# RTU_LMG_DI.net
KiCad netlist of a schematic drawn in Altium Designer
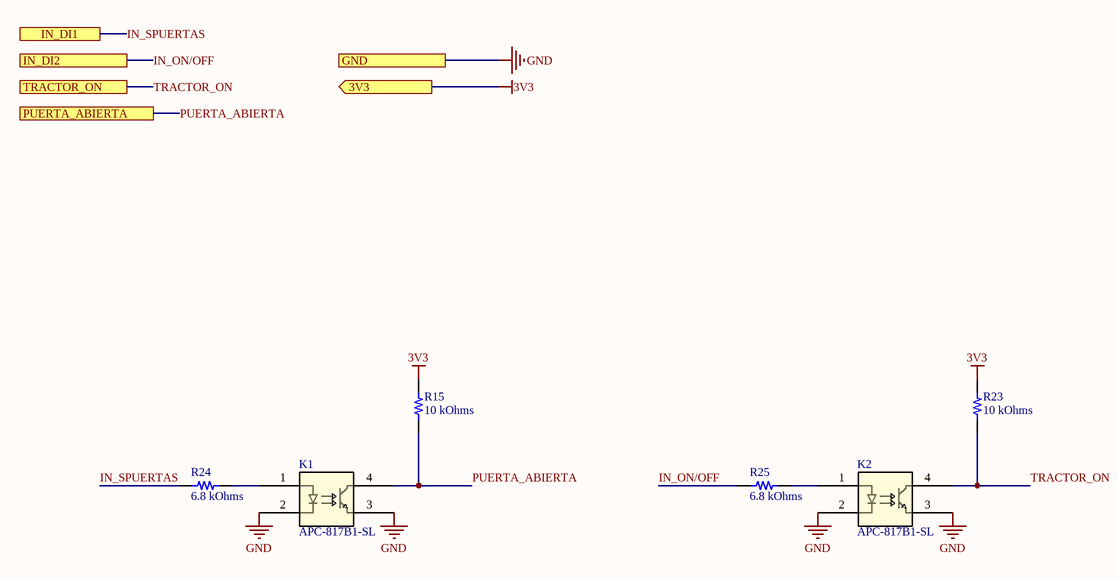
[diagram p0: RTU_LMG_DI.SchDoc]

(export (version "E")
  (design (tool "Eeschema 10.0.6"))
  (components
    (comp (ref "K1")
      (value "APC-817B1-SL")
      (footprint "APC-817xx-SL_AMB")
      (description "Description")
      (fields (field (name "COPYRIGHT") "Copyright (C) 2025 Ultra Librarian. All rights reserved."))
      (libsource (lib "APC-817B1-SL") (part "APC-817B1-SL"))
    )
    (comp (ref "K2")
      (value "APC-817B1-SL")
      (footprint "APC-817xx-SL_AMB")
      (description "Description")
      (fields (field (name "COPYRIGHT") "Copyright (C) 2025 Ultra Librarian. All rights reserved."))
      (libsource (lib "APC-817B1-SL") (part "APC-817B1-SL"))
    )
    (comp (ref "R15")
      (value "10 kOhms")
      (footprint "RES 0603_1608")
      (description "RES 10K OHM 1% 1/10W 0603")
      (fields (field (name "PART NUMBER") "RC0603FR-0710KL") (field (name "MANUFACTURER") "Yageo"))
      (libsource (lib "Celestial Altium Library - altium_library") (part "Resistor"))
    )
    (comp (ref "R23")
      (value "10 kOhms")
      (footprint "RES 0603_1608")
      (description "RES 10K OHM 1% 1/10W 0603")
      (fields (field (name "PART NUMBER") "RC0603FR-0710KL") (field (name "MANUFACTURER") "Yageo"))
      (libsource (lib "Celestial Altium Library - altium_library") (part "Resistor"))
    )
    (comp (ref "R24")
      (value "6.8 kOhms")
      (footprint "RES 0603_1608")
      (description "RES 6.8K OHM 5% 1/10W 0603")
      (fields
        (field (name "PART NUMBER") "RMCF0603JT6K80")
        (field (name "MANUFACTURER") "Stackpole Electronics Inc")
      )
      (libsource (lib "Celestial Altium Library - altium_library") (part "Resistor"))
    )
    (comp (ref "R25")
      (value "6.8 kOhms")
      (footprint "RES 0603_1608")
      (description "RES 6.8K OHM 5% 1/10W 0603")
      (fields
        (field (name "PART NUMBER") "RMCF0603JT6K80")
        (field (name "MANUFACTURER") "Stackpole Electronics Inc")
      )
      (libsource (lib "Celestial Altium Library - altium_library") (part "Resistor"))
    )
  )
  (nets
    (net (code "1") (name "/IN_ON{slash}OFF") (class "Default")
      (node (ref "R25") (pin "1") (pinfunction "1_1") (pintype "passive"))
    )
    (net (code "2") (name "/IN_SPUERTAS") (class "Default")
      (node (ref "R24") (pin "1") (pinfunction "1_1") (pintype "passive"))
    )
    (net (code "3") (name "/PUERTA_ABIERTA") (class "Default")
      (node (ref "K1") (pin "4") (pinfunction "4_4") (pintype "passive"))
      (node (ref "R15") (pin "1") (pinfunction "1_1") (pintype "passive"))
    )
    (net (code "4") (name "/TRACTOR_ON") (class "Default")
      (node (ref "K2") (pin "4") (pinfunction "4_4") (pintype "passive"))
      (node (ref "R23") (pin "1") (pinfunction "1_1") (pintype "passive"))
    )
    (net (code "5") (name "3V3") (class "Default")
      (node (ref "R15") (pin "2") (pinfunction "2_2") (pintype "passive"))
      (node (ref "R23") (pin "2") (pinfunction "2_2") (pintype "passive"))
    )
    (net (code "6") (name "GND") (class "Default")
      (node (ref "K1") (pin "2") (pinfunction "2_2") (pintype "passive"))
      (node (ref "K1") (pin "3") (pinfunction "3_3") (pintype "passive"))
      (node (ref "K2") (pin "2") (pinfunction "2_2") (pintype "passive"))
      (node (ref "K2") (pin "3") (pinfunction "3_3") (pintype "passive"))
    )
    (net (code "7") (name "Net-(K1-Pad1)") (class "Default")
      (node (ref "K1") (pin "1") (pinfunction "1_1") (pintype "passive"))
      (node (ref "R24") (pin "2") (pinfunction "2_2") (pintype "passive"))
    )
    (net (code "8") (name "Net-(K2-Pad1)") (class "Default")
      (node (ref "K2") (pin "1") (pinfunction "1_1") (pintype "passive"))
      (node (ref "R25") (pin "2") (pinfunction "2_2") (pintype "passive"))
    )
  )
)
